# ade7753.net
KiCad netlist of a schematic drawn in Altium Designer
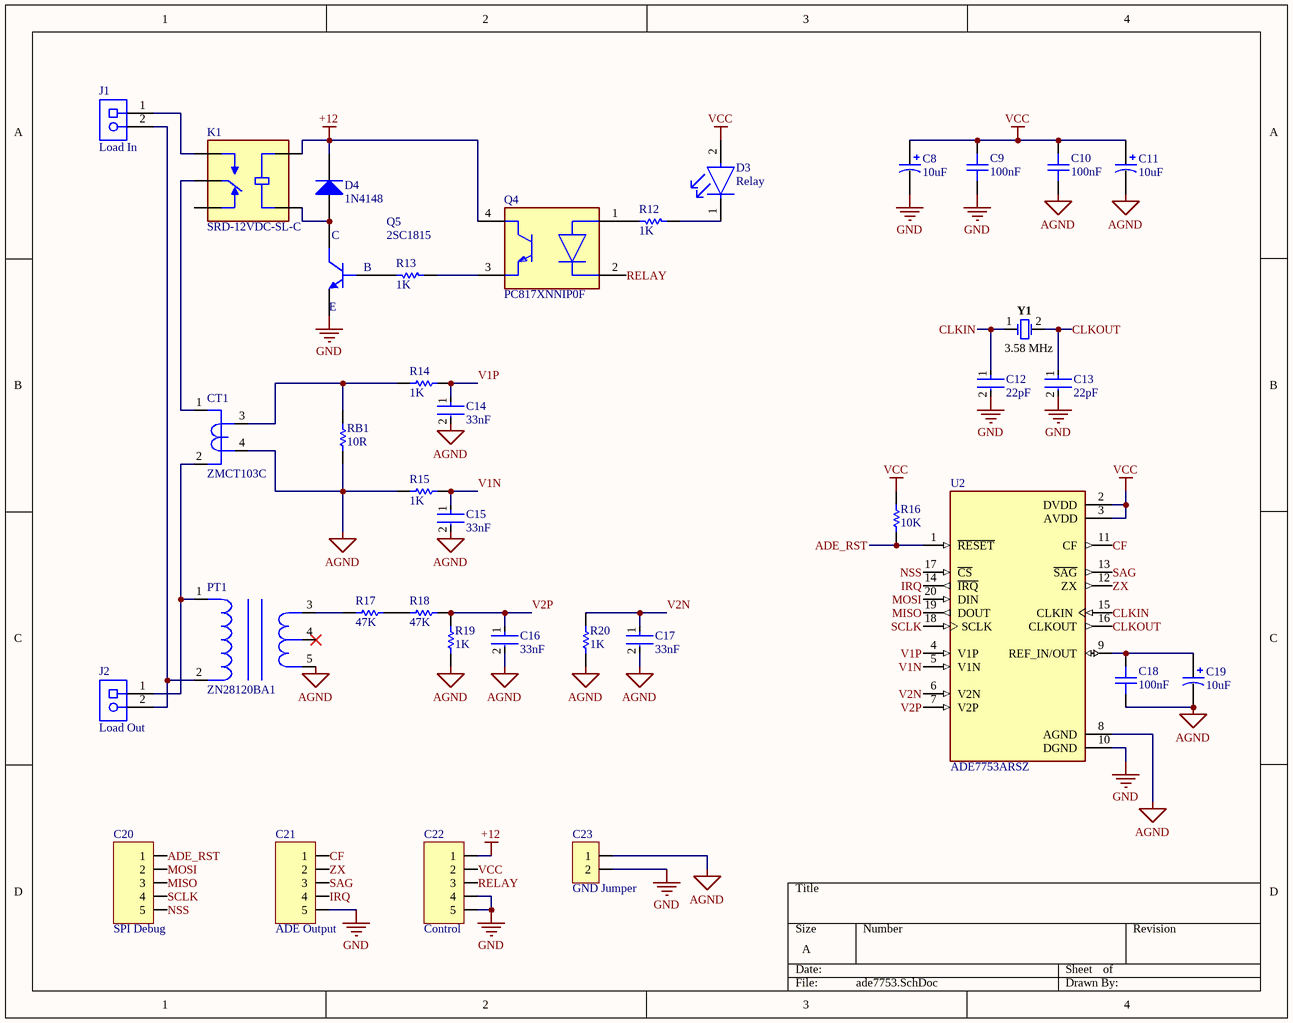
[diagram p0: ade7753.SchDoc]

(export (version "E")
  (design (tool "Eeschema 10.0.6"))
  (components
    (comp (ref "C8")
      (value "10uF")
      (footprint "CAP_ALUM_D050_S20_H110")
      (description "CAP ALUM 10uF 50V 20% RADIAL")
      (fields (field (name "MPN") "106CKR050M"))
      (libsource (lib "BYTECH_HW_LIB_2019") (part "106CKR050M"))
    )
    (comp (ref "C9")
      (value "100nF")
      (footprint "CAP_CER_TH100")
      (description "CAP CER 0.1uF -20 +80% 50V Y5V RADIAL")
      (fields (field (name "MPN") "K104Z15Y5VF5TL2"))
      (libsource (lib "BYTECH_HW_LIB_2019") (part "K104Z15Y5VF5TL2"))
    )
    (comp (ref "C10")
      (value "100nF")
      (footprint "CAP_CER_TH100")
      (description "CAP CER 0.1uF -20 +80% 50V Y5V RADIAL")
      (fields (field (name "MPN") "K104Z15Y5VF5TL2"))
      (libsource (lib "BYTECH_HW_LIB_2019") (part "K104Z15Y5VF5TL2"))
    )
    (comp (ref "C11")
      (value "10uF")
      (footprint "CAP_ALUM_D050_S20_H110")
      (description "CAP ALUM 10uF 50V 20% RADIAL")
      (fields (field (name "MPN") "106CKR050M"))
      (libsource (lib "BYTECH_HW_LIB_2019") (part "106CKR050M"))
    )
    (comp (ref "C12")
      (value "22pF")
      (footprint "FP-0603-L_1_6_0_15-W_0_81-IPC_A")
      (description "General Purpose Ceramic Capacitor, 0603, 22pF, 5%, NP0, 30ppm/°C, 50V")
      (fields (field (name "VOLTAGE") "50V") (field (name "TOLERANCE") "5%"))
      (libsource (lib "Altium Content Vault") (part "02cd4be3c70576c341d710602a673aa"))
    )
    (comp (ref "C13")
      (value "22pF")
      (footprint "FP-0603-L_1_6_0_15-W_0_81-IPC_A")
      (description "General Purpose Ceramic Capacitor, 0603, 22pF, 5%, NP0, 30ppm/°C, 50V")
      (fields (field (name "VOLTAGE") "50V") (field (name "TOLERANCE") "5%"))
      (libsource (lib "Altium Content Vault") (part "02cd4be3c70576c341d710602a673aa"))
    )
    (comp (ref "C14")
      (value "33nF")
      (footprint "FP-C0805C-DN-IPC_A")
      (description "CAP CER 0.033UF 50V X7R 0805")
      (fields
        (field (name "TOLERANCE") "0.1")
        (field (name "OCTOPART") "https://octopart.com/c0805c333k5ractu-kemet-142441")
      )
      (libsource (lib "Altium Content Vault") (part "b4654b650e69147ec39a6b967a45e02"))
    )
    (comp (ref "C15")
      (value "33nF")
      (footprint "FP-C0805C-DN-IPC_A")
      (description "CAP CER 0.033UF 50V X7R 0805")
      (fields
        (field (name "TOLERANCE") "0.1")
        (field (name "OCTOPART") "https://octopart.com/c0805c333k5ractu-kemet-142441")
      )
      (libsource (lib "Altium Content Vault") (part "b4654b650e69147ec39a6b967a45e02"))
    )
    (comp (ref "C16")
      (value "33nF")
      (footprint "FP-C0805C-DN-IPC_A")
      (description "CAP CER 0.033UF 50V X7R 0805")
      (fields
        (field (name "TOLERANCE") "0.1")
        (field (name "OCTOPART") "https://octopart.com/c0805c333k5ractu-kemet-142441")
      )
      (libsource (lib "Altium Content Vault") (part "b4654b650e69147ec39a6b967a45e02"))
    )
    (comp (ref "C17")
      (value "33nF")
      (footprint "FP-C0805C-DN-IPC_A")
      (description "CAP CER 0.033UF 50V X7R 0805")
      (fields
        (field (name "TOLERANCE") "0.1")
        (field (name "OCTOPART") "https://octopart.com/c0805c333k5ractu-kemet-142441")
      )
      (libsource (lib "Altium Content Vault") (part "b4654b650e69147ec39a6b967a45e02"))
    )
    (comp (ref "C18")
      (value "100nF")
      (footprint "CAP_CER_TH100")
      (description "CAP CER 0.1uF -20 +80% 50V Y5V RADIAL")
      (fields (field (name "MPN") "K104Z15Y5VF5TL2"))
      (libsource (lib "BYTECH_HW_LIB_2019") (part "K104Z15Y5VF5TL2"))
    )
    (comp (ref "C19")
      (value "10uF")
      (footprint "CAP_ALUM_D050_S20_H110")
      (description "CAP ALUM 10uF 50V 20% RADIAL")
      (fields (field (name "MPN") "106CKR050M"))
      (libsource (lib "BYTECH_HW_LIB_2019") (part "106CKR050M"))
    )
    (comp (ref "C20")
      (value "SPI Debug")
      (footprint "JP5-D1T")
      (description "WR-PHD 2.54 mm Angled Socket Header")
      (fields
        (field (name "MANUFACTURER") "Würth Elektronik eiSos GmbH")
        (field (name "PARTNO") "613005143121")
        (field (name "CREATED BY") "Karrer Zheng")
      )
      (libsource (lib "TechMT.VN_Lib_Project v2") (part "JP5"))
    )
    (comp (ref "C21")
      (value "ADE Output")
      (footprint "JP5-D1T")
      (description "WR-PHD 2.54 mm Angled Socket Header")
      (fields
        (field (name "MANUFACTURER") "Würth Elektronik eiSos GmbH")
        (field (name "PARTNO") "613005143121")
        (field (name "CREATED BY") "Karrer Zheng")
      )
      (libsource (lib "TechMT.VN_Lib_Project v2") (part "JP5"))
    )
    (comp (ref "C22")
      (value "Control")
      (footprint "JP5-D1T")
      (description "WR-PHD 2.54 mm Angled Socket Header")
      (fields
        (field (name "MANUFACTURER") "Würth Elektronik eiSos GmbH")
        (field (name "PARTNO") "613005143121")
        (field (name "CREATED BY") "Karrer Zheng")
      )
      (libsource (lib "TechMT.VN_Lib_Project v2") (part "JP5"))
    )
    (comp (ref "C23")
      (value "GND Jumper")
      (footprint "JP2-CLOSED")
      (description "WR-PHD 2.54 mm Angled Socket Header")
      (fields
        (field (name "MANUFACTURER") "Würth Elektronik eiSos GmbH")
        (field (name "PARTNO") "613002143121")
        (field (name "CREATED BY") "Karrer Zheng")
      )
      (libsource (lib "TechMT.VN_Lib_Project v2") (part "JP2"))
    )
    (comp (ref "CT1")
      (value "ZMCT103C")
      (footprint "ZMCT103C")
      (description "ZMCT103C Current Transformer 1000:1 5A/5mA")
      (libsource (lib "ZMCT103C") (part "ZMCT103C"))
    )
    (comp (ref "D3")
      (value "Relay")
      (footprint "FP-HLMP-4700-MFG")
      (description "LED RED DIFFUSED T-1 3/4 T/H")
      (fields
        (field (name "OCTOPART") "https://octopart.com/hlmp-4700-broadcom-71130526")
        (field (name "MANUFACTURER") "Broadcom")
      )
      (libsource (lib "Altium Content Vault") (part "8706943c75ba83719d021d2fdc84c58"))
    )
    (comp (ref "D4")
      (value "1N4148")
      (footprint "NXP-SOD27-2_V")
      (description "High-speed Diode, 100 V, 450 mA, 2-Pin SOD27, RoHS")
      (fields (field (name "MANUFACTURER") "NXP Semiconductors"))
      (libsource (lib "Altium Content Vault") (part "NXP-A1K2-2"))
    )
    (comp (ref "J1")
      (value "Load In")
      (footprint "PHOE-1729128-2_V")
      (description "PCB Terminal Block, 13.5 A, 400 V, 2-Pin THD, RoHS, Bulk")
      (fields (field (name "PARTNUMBER") "1729128") (field (name "MANUFACTURER") "Phoenix Contact"))
      (libsource (lib "Altium Content Vault") (part "CN-2P-F-R2"))
    )
    (comp (ref "J2")
      (value "Load Out")
      (footprint "PHOE-1729128-2_V")
      (description "PCB Terminal Block, 13.5 A, 400 V, 2-Pin THD, RoHS, Bulk")
      (fields (field (name "PARTNUMBER") "1729128") (field (name "MANUFACTURER") "Phoenix Contact"))
      (libsource (lib "Altium Content Vault") (part "CN-2P-F-R2"))
    )
    (comp (ref "K1")
      (value "SRD-12VDC-SL-C")
      (footprint "RELAY_SRD-12VDC-SL-C")
      (description "General Purpose Non Latching 12VDC SPDT Through Hole Relays RoHS")
      (fields (field (name "MF") "{'manufacturer': u'Songle Relay'}"))
      (libsource (lib "SnapEDA_Library") (part "SRD-12VDC-SL-C"))
    )
    (comp (ref "PT1")
      (value "ZN28120BA1")
      (footprint "ZN28120BA1")
      (description "220VAC / 12VAC EI28 ZN28120BA1")
      (libsource (lib "ZN28120BA1") (part "EI28 ZN28120BA1"))
    )
    (comp (ref "Q4")
      (value "PC817XNNIP0F")
      (footprint "FP-PC817XNNIP0F-MFG")
      (description "OPTOISOLATOR 5KV TRANS 4SMD")
      (libsource (lib "Altium Content Vault") (part "6470904bf6395c62928ee73e60120b8"))
    )
    (comp (ref "Q5")
      (value "2SC1815")
      (footprint "SOT23_3")
      (description "TRANS NPN 50V 0.15A SOT23-3")
      (libsource (lib "BYTECH_HW_LIB_2019") (part "2SC1815"))
    )
    (comp (ref "R12")
      (value "1K")
      (footprint "RESC1609X55X30ML15T15")
      (description "Chip Resistor, 10 KOhm, +/- 1%, 0.1 W, -55 to 155 degC, 0603 (1608 Metric), RoHS, Tape and Reel")
      (fields (field (name "TOLERANCE") "1%") (field (name "MANUFACTURER") "Panasonic"))
      (libsource (lib "Altium Content Vault") (part "RES-2"))
    )
    (comp (ref "R13")
      (value "1K")
      (footprint "RESC1609X55X30ML15T15")
      (description "Chip Resistor, 10 KOhm, +/- 1%, 0.1 W, -55 to 155 degC, 0603 (1608 Metric), RoHS, Tape and Reel")
      (fields (field (name "TOLERANCE") "1%") (field (name "MANUFACTURER") "Panasonic"))
      (libsource (lib "Altium Content Vault") (part "RES-2"))
    )
    (comp (ref "R14")
      (value "1K")
      (footprint "RESC1609X55X30ML15T15")
      (description "Chip Resistor, 10 KOhm, +/- 1%, 0.1 W, -55 to 155 degC, 0603 (1608 Metric), RoHS, Tape and Reel")
      (fields (field (name "TOLERANCE") "1%") (field (name "MANUFACTURER") "Panasonic"))
      (libsource (lib "Altium Content Vault") (part "RES-2"))
    )
    (comp (ref "R15")
      (value "1K")
      (footprint "RESC1609X55X30ML15T15")
      (description "Chip Resistor, 10 KOhm, +/- 1%, 0.1 W, -55 to 155 degC, 0603 (1608 Metric), RoHS, Tape and Reel")
      (fields (field (name "TOLERANCE") "1%") (field (name "MANUFACTURER") "Panasonic"))
      (libsource (lib "Altium Content Vault") (part "RES-2"))
    )
    (comp (ref "R16")
      (value "10K")
      (footprint "RESC1609X55X30ML15T15")
      (description "Chip Resistor, 10 KOhm, +/- 1%, 0.1 W, -55 to 155 degC, 0603 (1608 Metric), RoHS, Tape and Reel")
      (fields (field (name "TOLERANCE") "1%") (field (name "MANUFACTURER") "Panasonic"))
      (libsource (lib "Altium Content Vault") (part "RES-2"))
    )
    (comp (ref "R17")
      (value "47K")
      (footprint "RESC1609X55X30ML15T15")
      (description "Chip Resistor, 10 KOhm, +/- 1%, 0.1 W, -55 to 155 degC, 0603 (1608 Metric), RoHS, Tape and Reel")
      (fields (field (name "TOLERANCE") "1%") (field (name "MANUFACTURER") "Panasonic"))
      (libsource (lib "Altium Content Vault") (part "RES-2"))
    )
    (comp (ref "R18")
      (value "47K")
      (footprint "RESC1609X55X30ML15T15")
      (description "Chip Resistor, 10 KOhm, +/- 1%, 0.1 W, -55 to 155 degC, 0603 (1608 Metric), RoHS, Tape and Reel")
      (fields (field (name "TOLERANCE") "1%") (field (name "MANUFACTURER") "Panasonic"))
      (libsource (lib "Altium Content Vault") (part "RES-2"))
    )
    (comp (ref "R19")
      (value "1K")
      (footprint "RESC1609X55X30ML15T15")
      (description "Chip Resistor, 10 KOhm, +/- 1%, 0.1 W, -55 to 155 degC, 0603 (1608 Metric), RoHS, Tape and Reel")
      (fields (field (name "TOLERANCE") "1%") (field (name "MANUFACTURER") "Panasonic"))
      (libsource (lib "Altium Content Vault") (part "RES-2"))
    )
    (comp (ref "R20")
      (value "1K")
      (footprint "RESC1609X55X30ML15T15")
      (description "Chip Resistor, 10 KOhm, +/- 1%, 0.1 W, -55 to 155 degC, 0603 (1608 Metric), RoHS, Tape and Reel")
      (fields (field (name "TOLERANCE") "1%") (field (name "MANUFACTURER") "Panasonic"))
      (libsource (lib "Altium Content Vault") (part "RES-2"))
    )
    (comp (ref "RB1")
      (value "10R")
      (footprint "RESC1609X55X30ML15T15")
      (description "Chip Resistor, 10 KOhm, +/- 1%, 0.1 W, -55 to 155 degC, 0603 (1608 Metric), RoHS, Tape and Reel")
      (fields (field (name "TOLERANCE") "1%") (field (name "MANUFACTURER") "Panasonic"))
      (libsource (lib "Altium Content Vault") (part "RES-2"))
    )
    (comp (ref "U2")
      (value "ADE7753ARSZ")
      (footprint "SOP65P780X200-20N")
      (description "Single Phase Multifunction Metering IC 20-Pin SSOP Tube")
      (fields (field (name "MF") "{'manufacturer': u'Analog Devices'}"))
      (libsource (lib "SnapEDA_Library") (part "ADE7753ARSZ"))
    )
    (comp (ref "Y1")
      (value "3.58 MHz")
      (footprint "FOX-FOXSLF-2_V")
      (description "Resistance Weld Thru-Hole Crystal, 12 MHz, +/-30 ppm, -20 to 70 degC, 2-Pin THD, RoHS, Bulk")
      (libsource (lib "Altium Content Vault") (part "XTAL-1-2-2"))
    )
  )
  (nets
    (net (code "1") (name "+12") (class "Default")
      (node (ref "C22") (pin "1") (pinfunction "1_1") (pintype "passive"))
      (node (ref "D4") (pin "2") (pinfunction "K_2") (pintype "passive"))
      (node (ref "K1") (pin "COIL2") (pinfunction "COIL2_COIL2") (pintype "passive"))
      (node (ref "Q4") (pin "4") (pinfunction "C_4") (pintype "passive"))
    )
    (net (code "2") (name "/ADE_RST") (class "Default")
      (node (ref "C20") (pin "1") (pinfunction "1_1") (pintype "passive"))
      (node (ref "R16") (pin "1") (pinfunction "1_1") (pintype "passive"))
      (node (ref "U2") (pin "1") (pinfunction "~{RESET}_1") (pintype "input"))
    )
    (net (code "3") (name "/CF") (class "Default")
      (node (ref "C21") (pin "1") (pinfunction "1_1") (pintype "passive"))
      (node (ref "U2") (pin "11") (pinfunction "CF_11") (pintype "output"))
    )
    (net (code "4") (name "/CLKIN") (class "Default")
      (node (ref "C12") (pin "1") (pinfunction "1_1") (pintype "passive"))
      (node (ref "U2") (pin "15") (pinfunction "CLKIN_15") (pintype "input"))
      (node (ref "Y1") (pin "1") (pinfunction "1_1") (pintype "passive"))
    )
    (net (code "5") (name "/CLKOUT") (class "Default")
      (node (ref "C13") (pin "1") (pinfunction "1_1") (pintype "passive"))
      (node (ref "U2") (pin "16") (pinfunction "CLKOUT_16") (pintype "output"))
      (node (ref "Y1") (pin "2") (pinfunction "2_2") (pintype "passive"))
    )
    (net (code "6") (name "/IRQ") (class "Default")
      (node (ref "C21") (pin "4") (pinfunction "4_4") (pintype "passive"))
      (node (ref "U2") (pin "14") (pinfunction "~{IRQ}_14") (pintype "output"))
    )
    (net (code "7") (name "/MISO") (class "Default")
      (node (ref "C20") (pin "3") (pinfunction "3_3") (pintype "passive"))
      (node (ref "U2") (pin "19") (pinfunction "DOUT_19") (pintype "output"))
    )
    (net (code "8") (name "/MOSI") (class "Default")
      (node (ref "C20") (pin "2") (pinfunction "2_2") (pintype "passive"))
      (node (ref "U2") (pin "20") (pinfunction "DIN_20") (pintype "input"))
    )
    (net (code "9") (name "/NSS") (class "Default")
      (node (ref "C20") (pin "5") (pinfunction "5_5") (pintype "passive"))
      (node (ref "U2") (pin "17") (pinfunction "~{CS}_17") (pintype "input"))
    )
    (net (code "10") (name "/RELAY") (class "Default")
      (node (ref "C22") (pin "3") (pinfunction "3_3") (pintype "passive"))
      (node (ref "Q4") (pin "2") (pinfunction "C_2") (pintype "passive"))
    )
    (net (code "11") (name "/SAG") (class "Default")
      (node (ref "C21") (pin "3") (pinfunction "3_3") (pintype "passive"))
      (node (ref "U2") (pin "13") (pinfunction "~{SAG}_13") (pintype "output"))
    )
    (net (code "12") (name "/SCLK") (class "Default")
      (node (ref "C20") (pin "4") (pinfunction "4_4") (pintype "passive"))
      (node (ref "U2") (pin "18") (pinfunction "SCLK_18") (pintype "input"))
    )
    (net (code "13") (name "/V1N") (class "Default")
      (node (ref "C15") (pin "1") (pinfunction "1_1") (pintype "passive"))
      (node (ref "R15") (pin "2") (pinfunction "2_2") (pintype "passive"))
      (node (ref "U2") (pin "5") (pinfunction "V1N_5") (pintype "input"))
    )
    (net (code "14") (name "/V1P") (class "Default")
      (node (ref "C14") (pin "1") (pinfunction "1_1") (pintype "passive"))
      (node (ref "R14") (pin "2") (pinfunction "2_2") (pintype "passive"))
      (node (ref "U2") (pin "4") (pinfunction "V1P_4") (pintype "input"))
    )
    (net (code "15") (name "/V2N") (class "Default")
      (node (ref "C17") (pin "1") (pinfunction "1_1") (pintype "passive"))
      (node (ref "R20") (pin "2") (pinfunction "2_2") (pintype "passive"))
      (node (ref "U2") (pin "6") (pinfunction "V2N_6") (pintype "input"))
    )
    (net (code "16") (name "/V2P") (class "Default")
      (node (ref "C16") (pin "1") (pinfunction "1_1") (pintype "passive"))
      (node (ref "R18") (pin "1") (pinfunction "1_1") (pintype "passive"))
      (node (ref "R19") (pin "2") (pinfunction "2_2") (pintype "passive"))
      (node (ref "U2") (pin "7") (pinfunction "V2P_7") (pintype "input"))
    )
    (net (code "17") (name "/ZX") (class "Default")
      (node (ref "C21") (pin "2") (pinfunction "2_2") (pintype "passive"))
      (node (ref "U2") (pin "12") (pinfunction "ZX_12") (pintype "output"))
    )
    (net (code "18") (name "AGND") (class "Default")
      (node (ref "C10") (pin "1") (pinfunction "1_1") (pintype "passive"))
      (node (ref "C11") (pin "2") (pinfunction "2_2") (pintype "passive"))
      (node (ref "C14") (pin "2") (pinfunction "2_2") (pintype "passive"))
      (node (ref "C15") (pin "2") (pinfunction "2_2") (pintype "passive"))
      (node (ref "C16") (pin "2") (pinfunction "2_2") (pintype "passive"))
      (node (ref "C17") (pin "2") (pinfunction "2_2") (pintype "passive"))
      (node (ref "C18") (pin "1") (pinfunction "1_1") (pintype "passive"))
      (node (ref "C19") (pin "2") (pinfunction "2_2") (pintype "passive"))
      (node (ref "C23") (pin "1") (pinfunction "1_1") (pintype "passive"))
      (node (ref "CT1") (pin "4") (pinfunction "4_4") (pintype "passive"))
      (node (ref "PT1") (pin "5") (pinfunction "5_5") (pintype "passive"))
      (node (ref "R15") (pin "1") (pinfunction "1_1") (pintype "passive"))
      (node (ref "R19") (pin "1") (pinfunction "1_1") (pintype "passive"))
      (node (ref "R20") (pin "1") (pinfunction "1_1") (pintype "passive"))
      (node (ref "RB1") (pin "2") (pinfunction "2_2") (pintype "passive"))
      (node (ref "U2") (pin "8") (pinfunction "AGND_8") (pintype "power_in"))
    )
    (net (code "19") (name "GND") (class "Default")
      (node (ref "C12") (pin "2") (pinfunction "2_2") (pintype "passive"))
      (node (ref "C13") (pin "2") (pinfunction "2_2") (pintype "passive"))
      (node (ref "C21") (pin "5") (pinfunction "5_5") (pintype "passive"))
      (node (ref "C22") (pin "4") (pinfunction "4_4") (pintype "passive"))
      (node (ref "C22") (pin "5") (pinfunction "5_5") (pintype "passive"))
      (node (ref "C23") (pin "2") (pinfunction "2_2") (pintype "passive"))
      (node (ref "C8") (pin "2") (pinfunction "2_2") (pintype "passive"))
      (node (ref "C9") (pin "1") (pinfunction "1_1") (pintype "passive"))
      (node (ref "Q5") (pin "2") (pinfunction "E_2") (pintype "passive"))
      (node (ref "U2") (pin "10") (pinfunction "DGND_10") (pintype "power_in"))
    )
    (net (code "20") (name "Net-(CT1-Pad1)") (class "Default")
      (node (ref "CT1") (pin "1") (pinfunction "1_1") (pintype "passive"))
      (node (ref "K1") (pin "COM") (pinfunction "COM_COM") (pintype "passive"))
    )
    (net (code "21") (name "Net-(CT1-Pad2)") (class "Default")
      (node (ref "CT1") (pin "2") (pinfunction "2_2") (pintype "passive"))
      (node (ref "J2") (pin "1") (pinfunction "1_1") (pintype "passive"))
      (node (ref "PT1") (pin "1") (pinfunction "1_1") (pintype "passive"))
    )
    (net (code "22") (name "Net-(CT1-Pad3)") (class "Default")
      (node (ref "CT1") (pin "3") (pinfunction "3_3") (pintype "passive"))
      (node (ref "R14") (pin "1") (pinfunction "1_1") (pintype "passive"))
      (node (ref "RB1") (pin "1") (pinfunction "1_1") (pintype "passive"))
    )
    (net (code "23") (name "Net-(D3-C)") (class "Default")
      (node (ref "D3") (pin "1") (pinfunction "C_1") (pintype "passive"))
      (node (ref "R12") (pin "1") (pinfunction "1_1") (pintype "passive"))
    )
    (net (code "24") (name "Net-(D4-A)") (class "Default")
      (node (ref "D4") (pin "1") (pinfunction "A_1") (pintype "passive"))
      (node (ref "K1") (pin "COIL1") (pinfunction "COIL1_COIL1") (pintype "passive"))
      (node (ref "Q5") (pin "3") (pinfunction "C_3") (pintype "passive"))
    )
    (net (code "25") (name "Net-(J1-Pad1)") (class "Default")
      (node (ref "J1") (pin "1") (pinfunction "1_1") (pintype "passive"))
      (node (ref "K1") (pin "NO") (pinfunction "NO_NO") (pintype "passive"))
    )
    (net (code "26") (name "Net-(J1-Pad2)") (class "Default")
      (node (ref "J1") (pin "2") (pinfunction "2_2") (pintype "passive"))
      (node (ref "J2") (pin "2") (pinfunction "2_2") (pintype "passive"))
      (node (ref "PT1") (pin "2") (pinfunction "2_2") (pintype "passive"))
    )
    (net (code "27") (name "Net-(PT1-Pad3)") (class "Default")
      (node (ref "PT1") (pin "3") (pinfunction "3_3") (pintype "passive"))
      (node (ref "R17") (pin "2") (pinfunction "2_2") (pintype "passive"))
    )
    (net (code "28") (name "Net-(Q4-A)") (class "Default")
      (node (ref "Q4") (pin "1") (pinfunction "A_1") (pintype "passive"))
      (node (ref "R12") (pin "2") (pinfunction "2_2") (pintype "passive"))
    )
    (net (code "29") (name "Net-(Q4-E)") (class "Default")
      (node (ref "Q4") (pin "3") (pinfunction "E_3") (pintype "passive"))
      (node (ref "R13") (pin "1") (pinfunction "1_1") (pintype "passive"))
    )
    (net (code "30") (name "Net-(Q5-B)") (class "Default")
      (node (ref "Q5") (pin "1") (pinfunction "B_1") (pintype "passive"))
      (node (ref "R13") (pin "2") (pinfunction "2_2") (pintype "passive"))
    )
    (net (code "31") (name "Net-(R17-Pad1)") (class "Default")
      (node (ref "R17") (pin "1") (pinfunction "1_1") (pintype "passive"))
      (node (ref "R18") (pin "2") (pinfunction "2_2") (pintype "passive"))
    )
    (net (code "32") (name "Net-(U2-REF_IN{slash}OUT)") (class "Default")
      (node (ref "C18") (pin "2") (pinfunction "2_2") (pintype "passive"))
      (node (ref "C19") (pin "1") (pinfunction "1_1") (pintype "passive"))
      (node (ref "U2") (pin "9") (pinfunction "REF_IN/OUT_9") (pintype "bidirectional"))
    )
    (net (code "33") (name "VCC") (class "Default")
      (node (ref "C10") (pin "2") (pinfunction "2_2") (pintype "passive"))
      (node (ref "C11") (pin "1") (pinfunction "1_1") (pintype "passive"))
      (node (ref "C22") (pin "2") (pinfunction "2_2") (pintype "passive"))
      (node (ref "C8") (pin "1") (pinfunction "1_1") (pintype "passive"))
      (node (ref "C9") (pin "2") (pinfunction "2_2") (pintype "passive"))
      (node (ref "D3") (pin "2") (pinfunction "A_2") (pintype "passive"))
      (node (ref "R16") (pin "2") (pinfunction "2_2") (pintype "passive"))
      (node (ref "U2") (pin "2") (pinfunction "DVDD_2") (pintype "power_in"))
      (node (ref "U2") (pin "3") (pinfunction "AVDD_3") (pintype "power_in"))
    )
    (net (code "34") (name "unconnected-(K1-PadNC)") (class "Default")
      (node (ref "K1") (pin "NC") (pinfunction "NC_NC") (pintype "passive"))
    )
    (net (code "35") (name "unconnected-(PT1-Pad4)") (class "Default")
      (node (ref "PT1") (pin "4") (pinfunction "4_4") (pintype "passive+no_connect"))
    )
  )
)
